# bridge.net
KiCad netlist of a schematic drawn in EAGLE
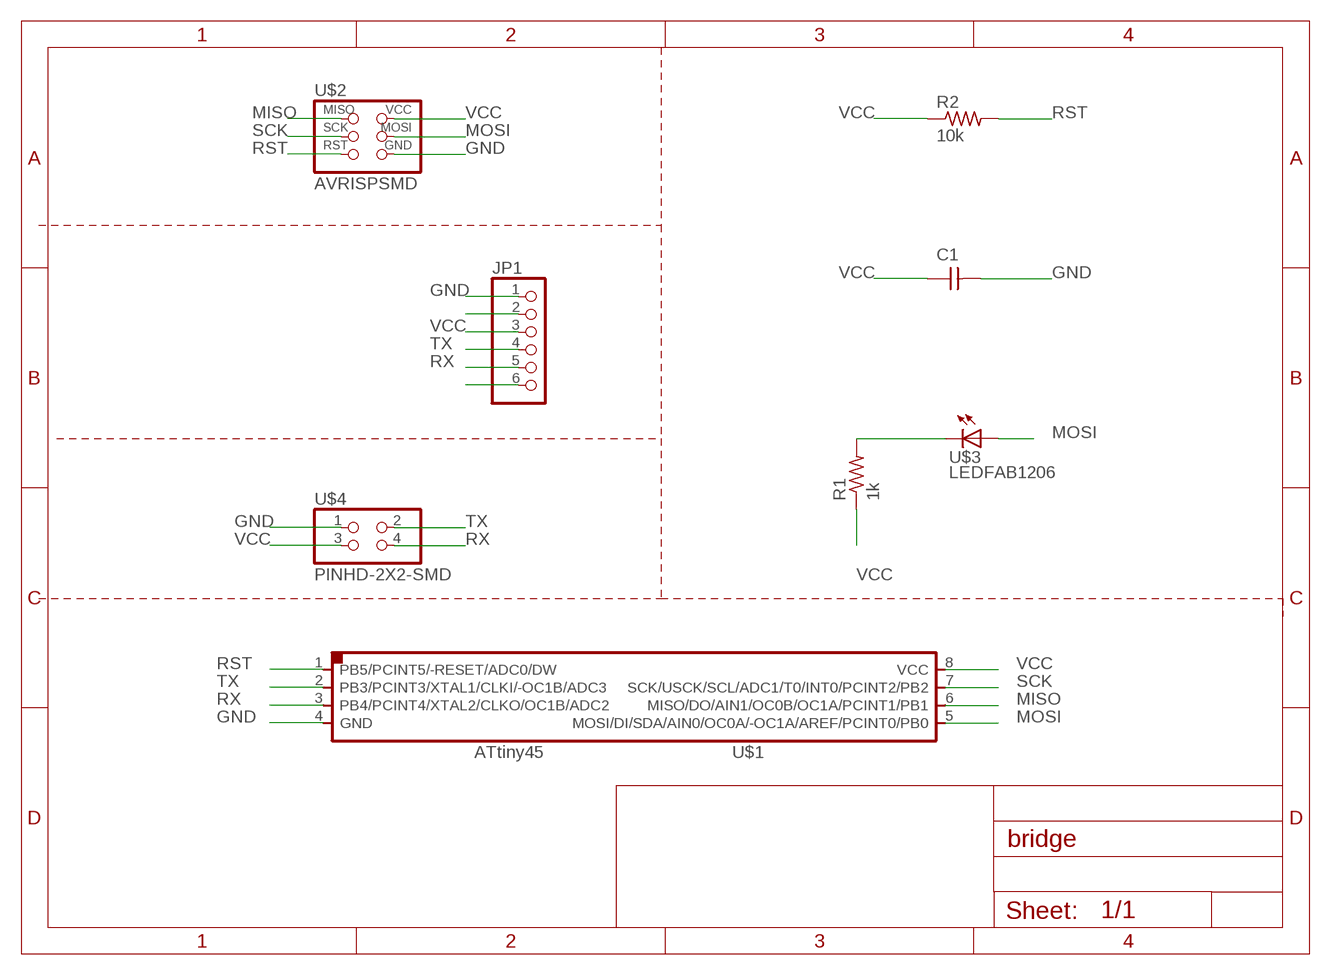
[diagram p0: schematic, sheet 1]

(export (version "E")
  (design (tool "Eeschema 10.0.6"))
  (components
    (comp (ref "C1")
      (value "CAP-UNPOLARIZEDFAB")
      (footprint "eagle-import:C1206FAB")
      (libsource (lib "eagle-import") (part "CAP-UNPOLARIZEDFAB"))
    )
    (comp (ref "JP1")
      (value "PINHD-1X6")
      (footprint "eagle-import:1X06")
      (libsource (lib "eagle-import") (part "PINHD-1X6"))
    )
    (comp (ref "R1")
      (value "1k")
      (footprint "eagle-import:R1206FAB")
      (libsource (lib "eagle-import") (part "RES-US1206FAB"))
    )
    (comp (ref "R2")
      (value "10k")
      (footprint "eagle-import:R1206FAB")
      (libsource (lib "eagle-import") (part "RES-US1206FAB"))
    )
    (comp (ref "U$1")
      (value "ATTINY45SI")
      (footprint "eagle-import:SOIC8")
      (libsource (lib "eagle-import") (part "ATTINY45SI"))
    )
    (comp (ref "U$2")
      (value "AVRISPSMD")
      (footprint "eagle-import:2X03SMD")
      (libsource (lib "eagle-import") (part "AVRISPSMD"))
    )
    (comp (ref "U$3")
      (value "LEDFAB1206")
      (footprint "eagle-import:LED1206FAB")
      (libsource (lib "eagle-import") (part "LEDFAB1206"))
    )
    (comp (ref "U$4")
      (value "PINHD-2X2-SMD")
      (footprint "eagle-import:2X02SMD")
      (libsource (lib "eagle-import") (part "PINHD-2X2-SMD"))
    )
  )
  (nets
    (net (code "1") (name "/GND") (class "Default")
      (node (ref "C1") (pin "2") (pinfunction "2_2") (pintype "passive"))
      (node (ref "JP1") (pin "1") (pinfunction "1_1") (pintype "passive"))
      (node (ref "U$1") (pin "4") (pinfunction "GND_4") (pintype "bidirectional"))
      (node (ref "U$2") (pin "6") (pinfunction "GND_6") (pintype "passive"))
      (node (ref "U$4") (pin "1") (pinfunction "1_1") (pintype "passive"))
    )
    (net (code "2") (name "/MISO") (class "Default")
      (node (ref "U$1") (pin "6") (pinfunction "MISO/DO/AIN1/OC0B/OC1A/PCINT1/PB1_6") (pintype "bidirectional"))
      (node (ref "U$2") (pin "1") (pinfunction "MISO_1") (pintype "passive"))
    )
    (net (code "3") (name "/MOSI") (class "Default")
      (node (ref "U$1") (pin "5") (pinfunction "MOSI/DI/SDA/AIN0/OC0A/-OC1A/AREF/PCINT0/PB0_5") (pintype "bidirectional"))
      (node (ref "U$2") (pin "4") (pinfunction "MOSI_4") (pintype "passive"))
      (node (ref "U$3") (pin "1") (pinfunction "A_1") (pintype "passive"))
    )
    (net (code "4") (name "/RST") (class "Default")
      (node (ref "R2") (pin "2") (pinfunction "2_2") (pintype "passive"))
      (node (ref "U$1") (pin "1") (pinfunction "PB5/PCINT5/-RESET/ADC0/DW_1") (pintype "bidirectional"))
      (node (ref "U$2") (pin "5") (pinfunction "RST_5") (pintype "passive"))
    )
    (net (code "5") (name "/RX") (class "Default")
      (node (ref "JP1") (pin "5") (pinfunction "5_5") (pintype "passive"))
      (node (ref "U$1") (pin "3") (pinfunction "PB4/PCINT4/XTAL2/CLKO/OC1B/ADC2_3") (pintype "bidirectional"))
      (node (ref "U$4") (pin "4") (pinfunction "4_4") (pintype "passive"))
    )
    (net (code "6") (name "/SCK") (class "Default")
      (node (ref "U$1") (pin "7") (pinfunction "SCK/USCK/SCL/ADC1/T0/INT0/PCINT2/PB2_7") (pintype "bidirectional"))
      (node (ref "U$2") (pin "3") (pinfunction "SCK_3") (pintype "passive"))
    )
    (net (code "7") (name "/TX") (class "Default")
      (node (ref "JP1") (pin "4") (pinfunction "4_4") (pintype "passive"))
      (node (ref "U$1") (pin "2") (pinfunction "PB3/PCINT3/XTAL1/CLKI/-OC1B/ADC3_2") (pintype "bidirectional"))
      (node (ref "U$4") (pin "2") (pinfunction "2_2") (pintype "passive"))
    )
    (net (code "8") (name "/VCC") (class "Default")
      (node (ref "C1") (pin "1") (pinfunction "1_1") (pintype "passive"))
      (node (ref "JP1") (pin "3") (pinfunction "3_3") (pintype "passive"))
      (node (ref "R1") (pin "1") (pinfunction "1_1") (pintype "passive"))
      (node (ref "R2") (pin "1") (pinfunction "1_1") (pintype "passive"))
      (node (ref "U$1") (pin "8") (pinfunction "VCC_8") (pintype "bidirectional"))
      (node (ref "U$2") (pin "2") (pinfunction "VCC_2") (pintype "passive"))
      (node (ref "U$4") (pin "3") (pinfunction "3_3") (pintype "passive"))
    )
    (net (code "9") (name "Net-(U$3-C)") (class "Default")
      (node (ref "R1") (pin "2") (pinfunction "2_2") (pintype "passive"))
      (node (ref "U$3") (pin "2") (pinfunction "C_2") (pintype "passive"))
    )
    (net (code "10") (name "unconnected-(JP1-Pad2)") (class "Default")
      (node (ref "JP1") (pin "2") (pinfunction "2_2") (pintype "passive"))
    )
    (net (code "11") (name "unconnected-(JP1-Pad6)") (class "Default")
      (node (ref "JP1") (pin "6") (pinfunction "6_6") (pintype "passive"))
    )
  )
)
